# RFM69HCW_BOB.net
KiCad netlist of a schematic drawn in EAGLE
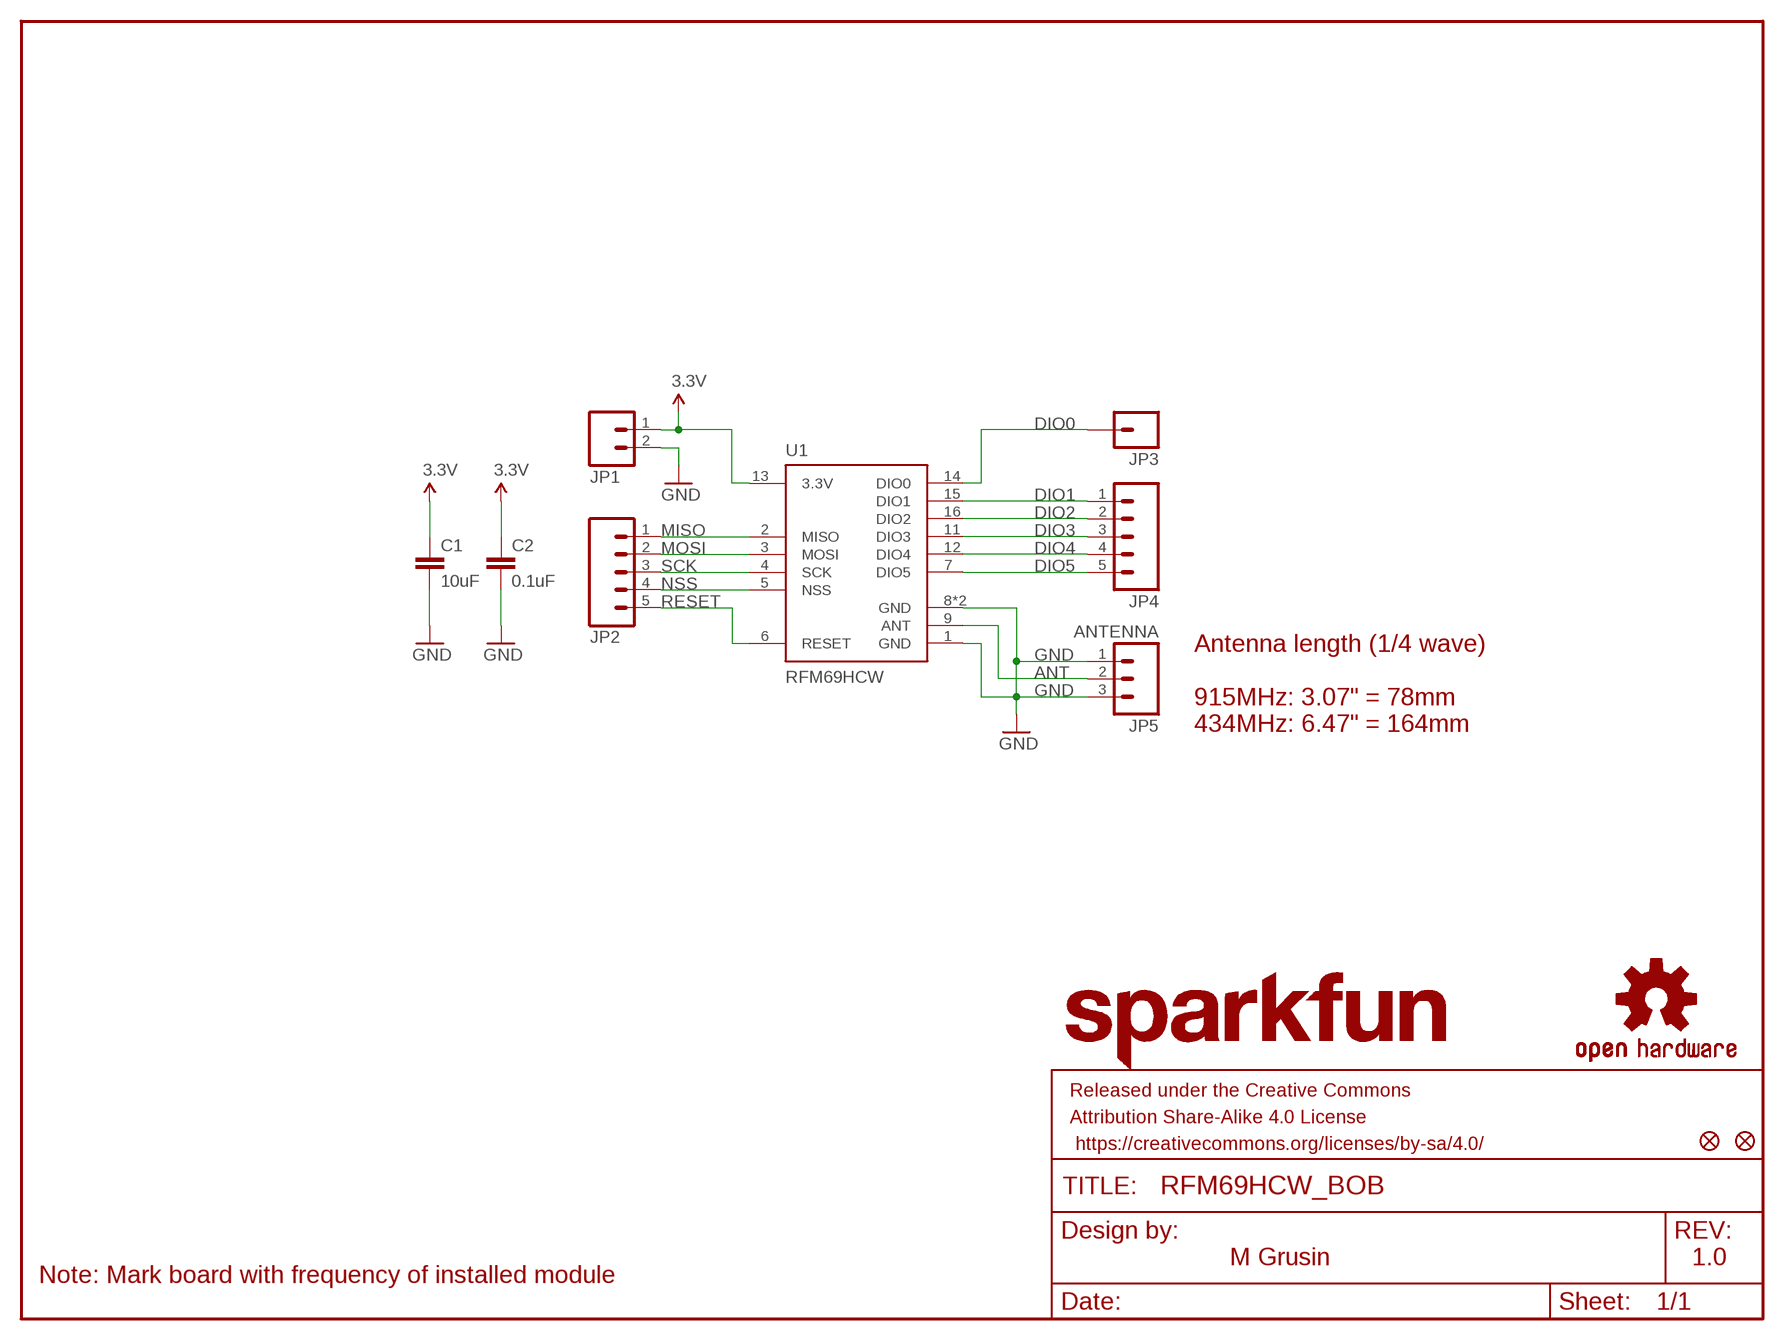
[diagram p0: schematic, sheet 1]

(export (version "E")
  (design (tool "Eeschema 10.0.6"))
  (components
    (comp (ref "C1")
      (value "10uF")
      (footprint "eagle-import:1210")
      (libsource (lib "eagle-import") (part "10UF50V20%(1210)"))
    )
    (comp (ref "C2")
      (value "0.1uF")
      (footprint "eagle-import:0603-CAP")
      (libsource (lib "eagle-import") (part "0.1UF-25V(+80/-20%)(0603)"))
    )
    (comp (ref "FID1")
      (value "FIDUCIAL1X2")
      (footprint "eagle-import:FIDUCIAL-1X2")
      (libsource (lib "eagle-import") (part "FIDUCIAL1X2"))
    )
    (comp (ref "FID2")
      (value "FIDUCIAL1X2")
      (footprint "eagle-import:FIDUCIAL-1X2")
      (libsource (lib "eagle-import") (part "FIDUCIAL1X2"))
    )
    (comp (ref "FRAME1")
      (value "FRAME-LETTER")
      (footprint "eagle-import:CREATIVE_COMMONS")
      (libsource (lib "eagle-import") (part "FRAME-LETTER"))
    )
    (comp (ref "JP1")
      (value "M021X02_NO_SILK")
      (footprint "eagle-import:1X02_NO_SILK")
      (libsource (lib "eagle-import") (part "M021X02_NO_SILK"))
    )
    (comp (ref "JP2")
      (value "M05_ROUNDONLY_NOSILK")
      (footprint "eagle-import:1X05_ROUNDONLY_NOSILK")
      (libsource (lib "eagle-import") (part "M05_ROUNDONLY_NOSILK"))
    )
    (comp (ref "JP3")
      (value "M01SMDNS")
      (footprint "eagle-import:1X01NS")
      (libsource (lib "eagle-import") (part "M01SMDNS"))
    )
    (comp (ref "JP4")
      (value "M05_ROUNDONLY_NOSILK")
      (footprint "eagle-import:1X05_ROUNDONLY_NOSILK")
      (libsource (lib "eagle-import") (part "M05_ROUNDONLY_NOSILK"))
    )
    (comp (ref "JP5")
      (value "ANTENNA")
      (footprint "eagle-import:1X03_ROUND_ONLY_NO_SILK")
      (libsource (lib "eagle-import") (part "M03_ROUND_ONLY_NO_SILK"))
    )
    (comp (ref "LOGO1")
      (value "SFE_LOGO_NAME.1_INCH")
      (footprint "eagle-import:SFE_LOGO_NAME_.1")
      (libsource (lib "eagle-import") (part "SFE_LOGO_NAME.1_INCH"))
    )
    (comp (ref "LOGO2")
      (value "OSHW-LOGOS")
      (footprint "eagle-import:OSHW-LOGO-S")
      (libsource (lib "eagle-import") (part "OSHW-LOGOS"))
    )
    (comp (ref "U1")
      (value "RFM69HCW")
      (footprint "eagle-import:RFM69HCW-XXXS2")
      (libsource (lib "eagle-import") (part "RFM69HCW"))
    )
  )
  (nets
    (net (code "1") (name "/ANT") (class "Default")
      (node (ref "JP5") (pin "2") (pinfunction "2_2") (pintype "passive"))
      (node (ref "U1") (pin "9") (pinfunction "ANT_9") (pintype "passive"))
    )
    (net (code "2") (name "/DIO0") (class "Default")
      (node (ref "JP3") (pin "1") (pinfunction "1_1") (pintype "passive"))
      (node (ref "U1") (pin "14") (pinfunction "DIO0_14") (pintype "bidirectional"))
    )
    (net (code "3") (name "/DIO1") (class "Default")
      (node (ref "JP4") (pin "1") (pinfunction "1_1") (pintype "passive"))
      (node (ref "U1") (pin "15") (pinfunction "DIO1_15") (pintype "bidirectional"))
    )
    (net (code "4") (name "/DIO2") (class "Default")
      (node (ref "JP4") (pin "2") (pinfunction "2_2") (pintype "passive"))
      (node (ref "U1") (pin "16") (pinfunction "DIO2_16") (pintype "bidirectional"))
    )
    (net (code "5") (name "/DIO3") (class "Default")
      (node (ref "JP4") (pin "3") (pinfunction "3_3") (pintype "passive"))
      (node (ref "U1") (pin "11") (pinfunction "DIO3_11") (pintype "bidirectional"))
    )
    (net (code "6") (name "/DIO4") (class "Default")
      (node (ref "JP4") (pin "4") (pinfunction "4_4") (pintype "passive"))
      (node (ref "U1") (pin "12") (pinfunction "DIO4_12") (pintype "bidirectional"))
    )
    (net (code "7") (name "/DIO5") (class "Default")
      (node (ref "JP4") (pin "5") (pinfunction "5_5") (pintype "passive"))
      (node (ref "U1") (pin "7") (pinfunction "DIO5_7") (pintype "bidirectional"))
    )
    (net (code "8") (name "/MISO") (class "Default")
      (node (ref "JP2") (pin "1") (pinfunction "1_1") (pintype "passive"))
      (node (ref "U1") (pin "2") (pinfunction "MISO_2") (pintype "bidirectional"))
    )
    (net (code "9") (name "/MOSI") (class "Default")
      (node (ref "JP2") (pin "2") (pinfunction "2_2") (pintype "passive"))
      (node (ref "U1") (pin "3") (pinfunction "MOSI_3") (pintype "input"))
    )
    (net (code "10") (name "/NSS") (class "Default")
      (node (ref "JP2") (pin "4") (pinfunction "4_4") (pintype "passive"))
      (node (ref "U1") (pin "5") (pinfunction "NSS_5") (pintype "input"))
    )
    (net (code "11") (name "/RESET") (class "Default")
      (node (ref "JP2") (pin "5") (pinfunction "5_5") (pintype "passive"))
      (node (ref "U1") (pin "6") (pinfunction "RESET_6") (pintype "input"))
    )
    (net (code "12") (name "/SCK") (class "Default")
      (node (ref "JP2") (pin "3") (pinfunction "3_3") (pintype "passive"))
      (node (ref "U1") (pin "4") (pinfunction "SCK_4") (pintype "input"))
    )
    (net (code "13") (name "3.3V") (class "Default")
      (node (ref "C1") (pin "1") (pinfunction "1_1") (pintype "passive"))
      (node (ref "C2") (pin "1") (pinfunction "1_1") (pintype "passive"))
      (node (ref "JP1") (pin "1") (pinfunction "1_1") (pintype "passive"))
      (node (ref "U1") (pin "13") (pinfunction "3.3V_13") (pintype "power_in"))
    )
    (net (code "14") (name "GND") (class "Default")
      (node (ref "C1") (pin "2") (pinfunction "2_2") (pintype "passive"))
      (node (ref "C2") (pin "2") (pinfunction "2_2") (pintype "passive"))
      (node (ref "JP1") (pin "2") (pinfunction "2_2") (pintype "passive"))
      (node (ref "JP5") (pin "1") (pinfunction "1_1") (pintype "passive"))
      (node (ref "JP5") (pin "3") (pinfunction "3_3") (pintype "passive"))
      (node (ref "U1") (pin "1") (pinfunction "GND_1") (pintype "power_in"))
      (node (ref "U1") (pin "10") (pinfunction "GND_10") (pintype "power_in"))
      (node (ref "U1") (pin "8") (pinfunction "GND_8") (pintype "power_in"))
    )
  )
)
